# A04_HARD_PROTECT.net
KiCad netlist of a schematic drawn in Altium Designer
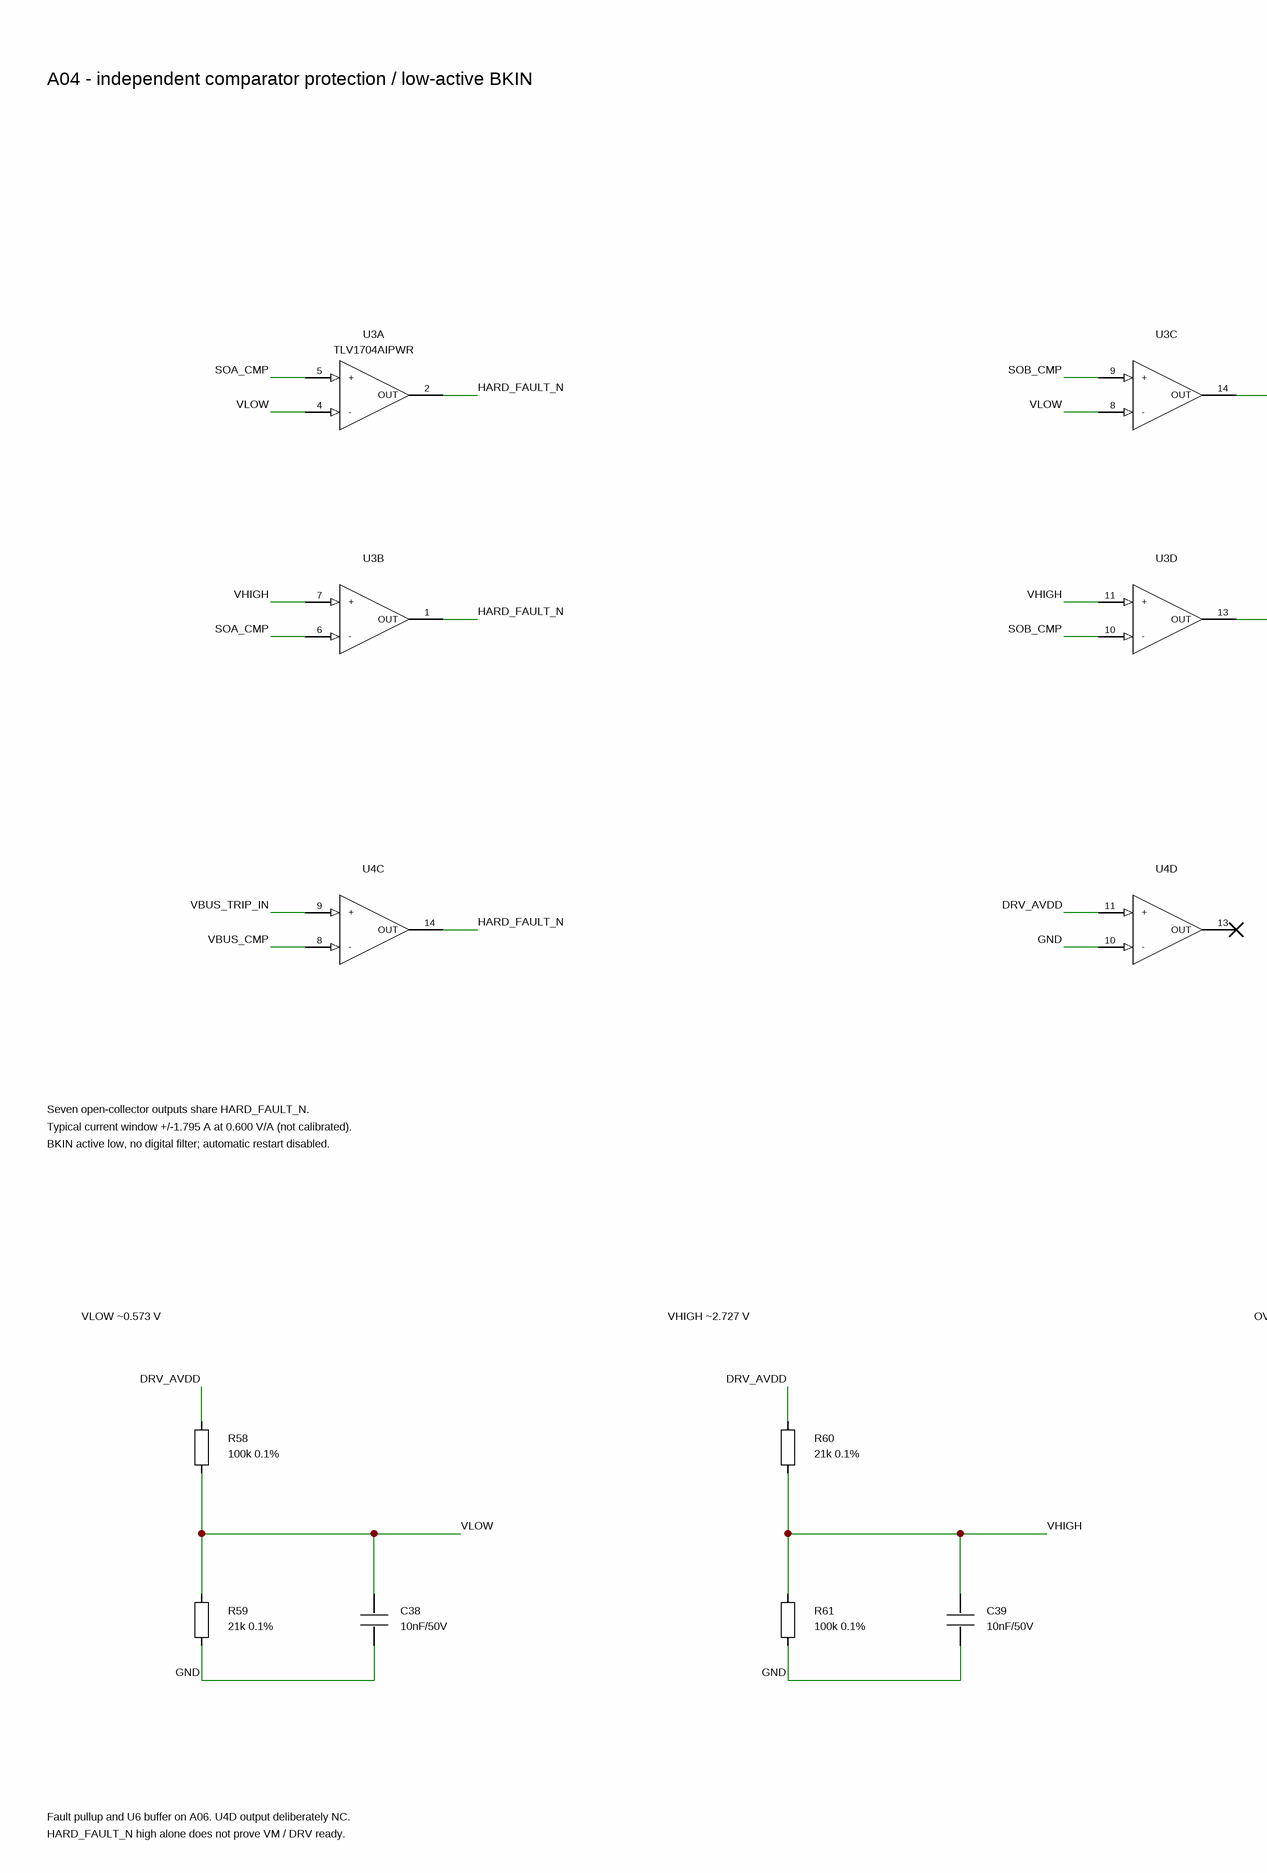
[diagram p0: A04_HARD_PROTECT.SchDoc, left]
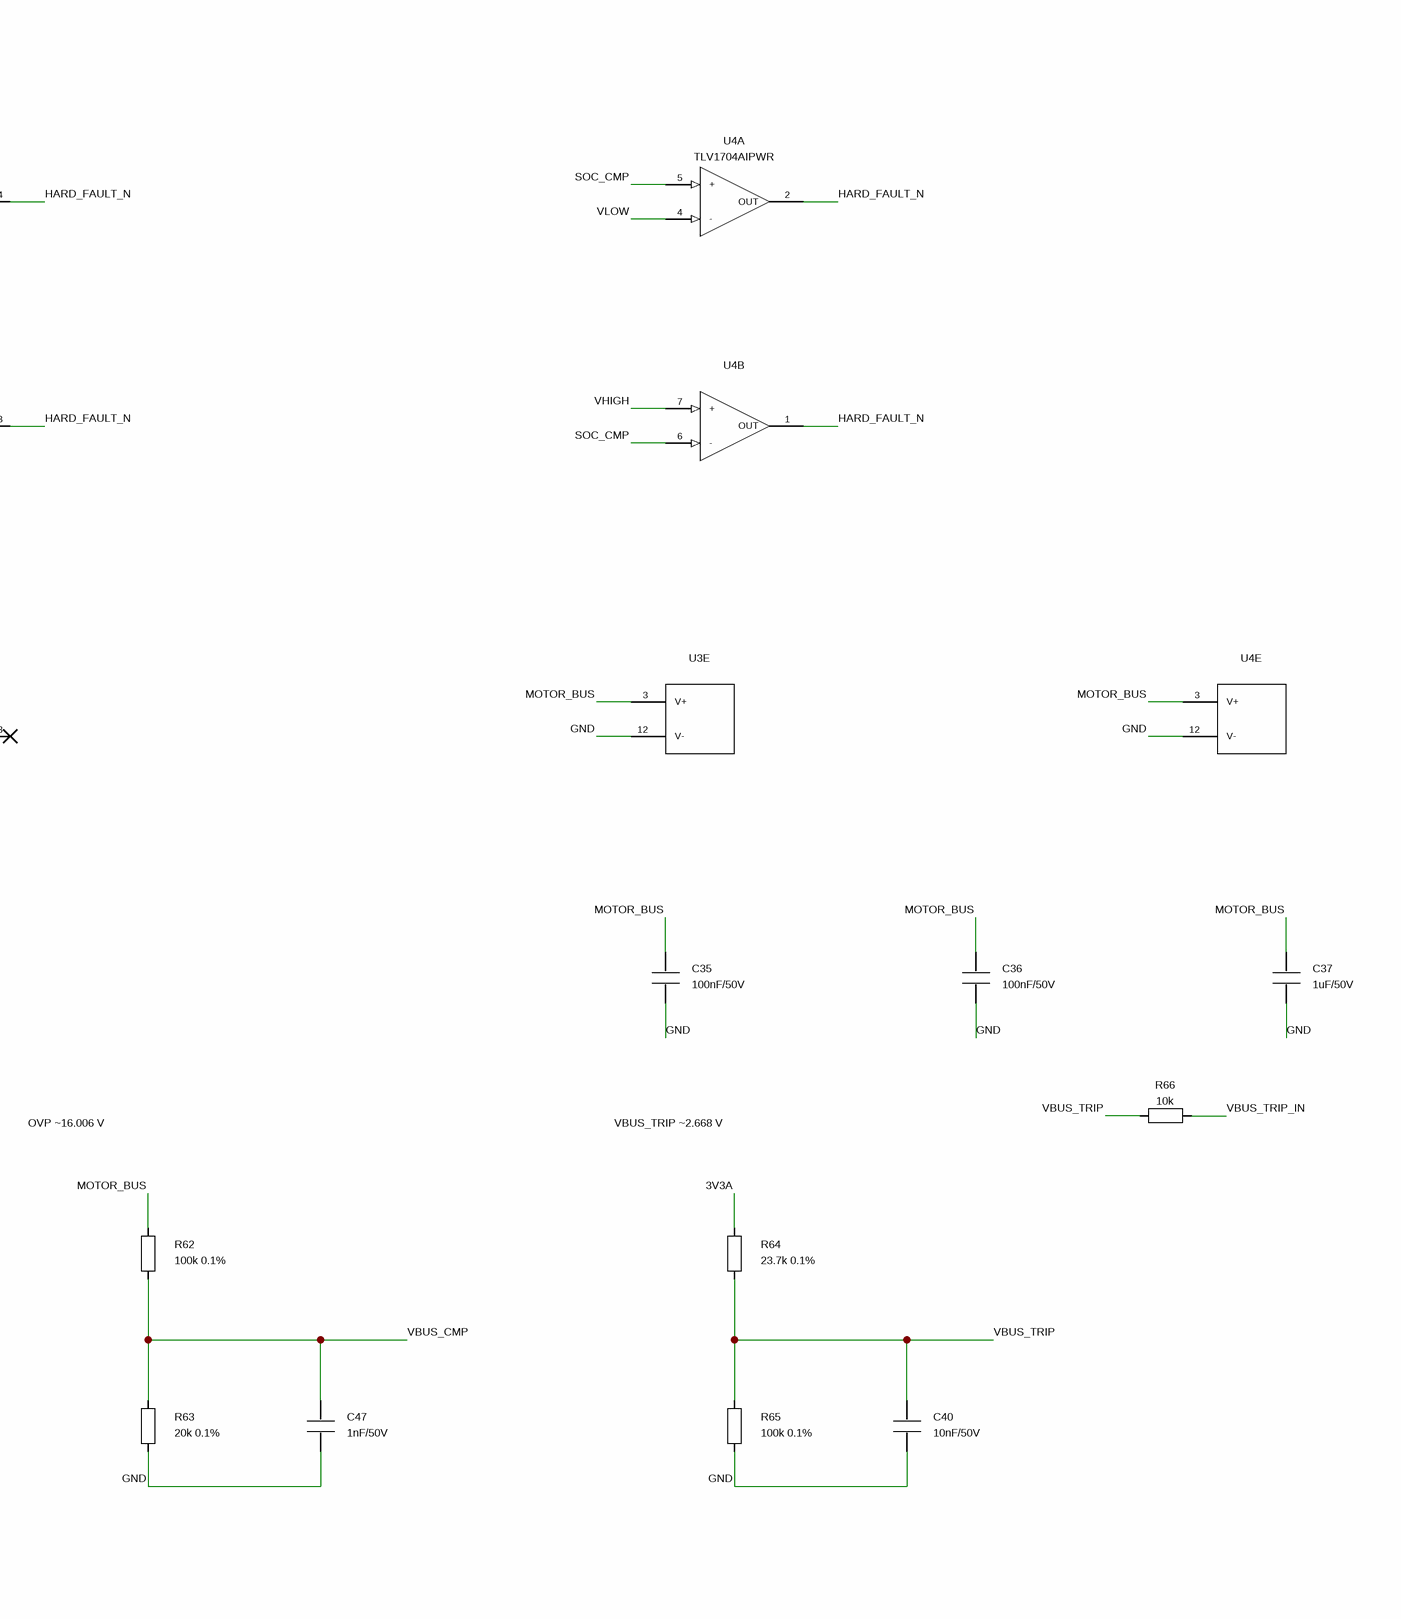
[diagram p1: A04_HARD_PROTECT.SchDoc, right]

(export (version "E")
  (design (tool "Eeschema 10.0.6"))
  (components
    (comp (ref "C35")
      (value "100nF/50V")
      (footprint "User_STM32F407_Ctrl:C0603_M")
      (description "电容")
      (fields (field (name "MPN") "CL10B104KB8NNNC"))
      (libsource (lib "altium-import") (part "root_0_C_"))
    )
    (comp (ref "C36")
      (value "100nF/50V")
      (footprint "User_STM32F407_Ctrl:C0603_M")
      (description "电容")
      (fields (field (name "MPN") "CL10B104KB8NNNC"))
      (libsource (lib "altium-import") (part "root_0_C_"))
    )
    (comp (ref "C37")
      (value "1uF/50V")
      (footprint "User_STM32F407_Ctrl:C0805_M")
      (description "电容")
      (fields (field (name "MPN") "CL21B105KBFNNNE"))
      (libsource (lib "altium-import") (part "root_0_C_"))
    )
    (comp (ref "C38")
      (value "10nF/50V")
      (footprint "User_STM32F407_Ctrl:C0603_M")
      (description "电容")
      (fields (field (name "MPN") "CC0603KRX7R9BB103"))
      (libsource (lib "altium-import") (part "root_0_C_"))
    )
    (comp (ref "C39")
      (value "10nF/50V")
      (footprint "User_STM32F407_Ctrl:C0603_M")
      (description "电容")
      (fields (field (name "MPN") "CC0603KRX7R9BB103"))
      (libsource (lib "altium-import") (part "root_0_C_"))
    )
    (comp (ref "C40")
      (value "10nF/50V")
      (footprint "User_STM32F407_Ctrl:C0603_M")
      (description "电容")
      (fields (field (name "MPN") "CC0603KRX7R9BB103"))
      (libsource (lib "altium-import") (part "root_0_C_"))
    )
    (comp (ref "C47")
      (value "1nF/50V")
      (footprint "User_STM32F407_Ctrl:C0603_M")
      (description "电容")
      (fields (field (name "MPN") "CL10B102KB8NNNC"))
      (libsource (lib "altium-import") (part "root_0_C_"))
    )
    (comp (ref "R58")
      (value "100k 0.1%")
      (footprint "User_STM32F407_Ctrl:R0603_M")
      (description "电阻")
      (fields (field (name "MPN") "RT0603BRD07100KL"))
      (libsource (lib "altium-import") (part "root_0_R_"))
    )
    (comp (ref "R59")
      (value "21k 0.1%")
      (footprint "User_STM32F407_Ctrl:R0603_M")
      (description "电阻")
      (fields (field (name "MPN") "PTFR0603B21K0N9"))
      (libsource (lib "altium-import") (part "root_0_R_"))
    )
    (comp (ref "R60")
      (value "21k 0.1%")
      (footprint "User_STM32F407_Ctrl:R0603_M")
      (description "电阻")
      (fields (field (name "MPN") "PTFR0603B21K0N9"))
      (libsource (lib "altium-import") (part "root_0_R_"))
    )
    (comp (ref "R61")
      (value "100k 0.1%")
      (footprint "User_STM32F407_Ctrl:R0603_M")
      (description "电阻")
      (fields (field (name "MPN") "RT0603BRD07100KL"))
      (libsource (lib "altium-import") (part "root_0_R_"))
    )
    (comp (ref "R62")
      (value "100k 0.1%")
      (footprint "User_STM32F407_Ctrl:R0603_M")
      (description "电阻")
      (fields (field (name "MPN") "RT0603BRD07100KL"))
      (libsource (lib "altium-import") (part "root_0_R_"))
    )
    (comp (ref "R63")
      (value "20k 0.1%")
      (footprint "User_STM32F407_Ctrl:R0603_M")
      (description "电阻")
      (fields (field (name "MPN") "TNPW060320K0BEEA"))
      (libsource (lib "altium-import") (part "root_0_R_"))
    )
    (comp (ref "R64")
      (value "23.7k 0.1%")
      (footprint "User_STM32F407_Ctrl:R0603_M")
      (description "电阻")
      (fields (field (name "MPN") "AT0603BRD0723K7L"))
      (libsource (lib "altium-import") (part "root_0_R_"))
    )
    (comp (ref "R65")
      (value "100k 0.1%")
      (footprint "User_STM32F407_Ctrl:R0603_M")
      (description "电阻")
      (fields (field (name "MPN") "RT0603BRD07100KL"))
      (libsource (lib "altium-import") (part "root_0_R_"))
    )
    (comp (ref "R66")
      (value "10k")
      (footprint "User_STM32F407_Ctrl:R0603_M")
      (description "电阻")
      (fields (field (name "MPN") "通用厚膜 10k 1% 0.1 W"))
      (libsource (lib "altium-import") (part "root_1_R_"))
    )
    (comp (ref "U3")
      (value "TLV1704AIPWR")
      (footprint "User_LCSC:C181596_TSSOP-14")
      (description "四路比较器")
      (libsource (lib "") (part "root_0_TLV1704AIPWR__2"))
    )
    (comp (ref "U4")
      (value "TLV1704AIPWR")
      (footprint "User_LCSC:C181596_TSSOP-14")
      (description "四路比较器")
      (libsource (lib "") (part "root_0_TLV1704AIPWR__2"))
    )
  )
  (nets
    (net (code "1") (name "/3V3A") (class "Default") (node (ref "R64") (pin "1") (pintype "passive")))
    (net (code "2") (name "/DRV_AVDD") (class "Default")
      (node (ref "R58") (pin "1") (pintype "passive"))
      (node (ref "R60") (pin "1") (pintype "passive"))
      (node (ref "U4") (pin "11") (pinfunction "+_11") (pintype "input"))
    )
    (net (code "3") (name "/GND") (class "Default")
      (node (ref "C35") (pin "2") (pintype "passive"))
      (node (ref "C36") (pin "2") (pintype "passive"))
      (node (ref "C37") (pin "2") (pintype "passive"))
      (node (ref "C38") (pin "2") (pintype "passive"))
      (node (ref "C39") (pin "2") (pintype "passive"))
      (node (ref "C40") (pin "2") (pintype "passive"))
      (node (ref "C47") (pin "2") (pintype "passive"))
      (node (ref "R59") (pin "2") (pintype "passive"))
      (node (ref "R61") (pin "2") (pintype "passive"))
      (node (ref "R63") (pin "2") (pintype "passive"))
      (node (ref "R65") (pin "2") (pintype "passive"))
      (node (ref "U3") (pin "12") (pinfunction "V-_12") (pintype "power_in"))
      (node (ref "U4") (pin "10") (pinfunction "-_10") (pintype "input"))
      (node (ref "U4") (pin "12") (pinfunction "V-_12") (pintype "power_in"))
    )
    (net (code "4") (name "/HARD_FAULT_N") (class "Default")
      (node (ref "U3") (pin "1") (pinfunction "OUT_1") (pintype "open_collector"))
      (node (ref "U3") (pin "13") (pinfunction "OUT_13") (pintype "open_collector"))
      (node (ref "U3") (pin "14") (pinfunction "OUT_14") (pintype "open_collector"))
      (node (ref "U3") (pin "2") (pinfunction "OUT_2") (pintype "open_collector"))
      (node (ref "U4") (pin "1") (pinfunction "OUT_1") (pintype "open_collector"))
      (node (ref "U4") (pin "14") (pinfunction "OUT_14") (pintype "open_collector"))
      (node (ref "U4") (pin "2") (pinfunction "OUT_2") (pintype "open_collector"))
    )
    (net (code "5") (name "/MOTOR_BUS") (class "Default")
      (node (ref "C35") (pin "1") (pintype "passive"))
      (node (ref "C36") (pin "1") (pintype "passive"))
      (node (ref "C37") (pin "1") (pintype "passive"))
      (node (ref "R62") (pin "1") (pintype "passive"))
      (node (ref "U3") (pin "3") (pinfunction "V+_3") (pintype "power_in"))
      (node (ref "U4") (pin "3") (pinfunction "V+_3") (pintype "power_in"))
    )
    (net (code "6") (name "/SOA_CMP") (class "Default")
      (node (ref "U3") (pin "5") (pinfunction "+_5") (pintype "input"))
      (node (ref "U3") (pin "6") (pinfunction "-_6") (pintype "input"))
    )
    (net (code "7") (name "/SOB_CMP") (class "Default")
      (node (ref "U3") (pin "10") (pinfunction "-_10") (pintype "input"))
      (node (ref "U3") (pin "9") (pinfunction "+_9") (pintype "input"))
    )
    (net (code "8") (name "/SOC_CMP") (class "Default")
      (node (ref "U4") (pin "5") (pinfunction "+_5") (pintype "input"))
      (node (ref "U4") (pin "6") (pinfunction "-_6") (pintype "input"))
    )
    (net (code "9") (name "/VBUS_CMP") (class "Default")
      (node (ref "C47") (pin "1") (pintype "passive"))
      (node (ref "R62") (pin "2") (pintype "passive"))
      (node (ref "R63") (pin "1") (pintype "passive"))
      (node (ref "U4") (pin "8") (pinfunction "-_8") (pintype "input"))
    )
    (net (code "10") (name "/VBUS_TRIP") (class "Default")
      (node (ref "C40") (pin "1") (pintype "passive"))
      (node (ref "R64") (pin "2") (pintype "passive"))
      (node (ref "R65") (pin "1") (pintype "passive"))
      (node (ref "R66") (pin "1") (pintype "passive"))
    )
    (net (code "11") (name "/VBUS_TRIP_IN") (class "Default")
      (node (ref "R66") (pin "2") (pintype "passive"))
      (node (ref "U4") (pin "9") (pinfunction "+_9") (pintype "input"))
    )
    (net (code "12") (name "/VHIGH") (class "Default")
      (node (ref "C39") (pin "1") (pintype "passive"))
      (node (ref "R60") (pin "2") (pintype "passive"))
      (node (ref "R61") (pin "1") (pintype "passive"))
      (node (ref "U3") (pin "11") (pinfunction "+_11") (pintype "input"))
      (node (ref "U3") (pin "7") (pinfunction "+_7") (pintype "input"))
      (node (ref "U4") (pin "7") (pinfunction "+_7") (pintype "input"))
    )
    (net (code "13") (name "/VLOW") (class "Default")
      (node (ref "C38") (pin "1") (pintype "passive"))
      (node (ref "R58") (pin "2") (pintype "passive"))
      (node (ref "R59") (pin "1") (pintype "passive"))
      (node (ref "U3") (pin "4") (pinfunction "-_4") (pintype "input"))
      (node (ref "U3") (pin "8") (pinfunction "-_8") (pintype "input"))
      (node (ref "U4") (pin "4") (pinfunction "-_4") (pintype "input"))
    )
    (net (code "14") (name "unconnected-(U4D-OUT-Pad13)") (class "Default")
      (node (ref "U4") (pin "13") (pinfunction "OUT_13") (pintype "open_collector+no_connect"))
    )
  )
)
